# graphic.net
KiCad netlist of a schematic drawn in EAGLE
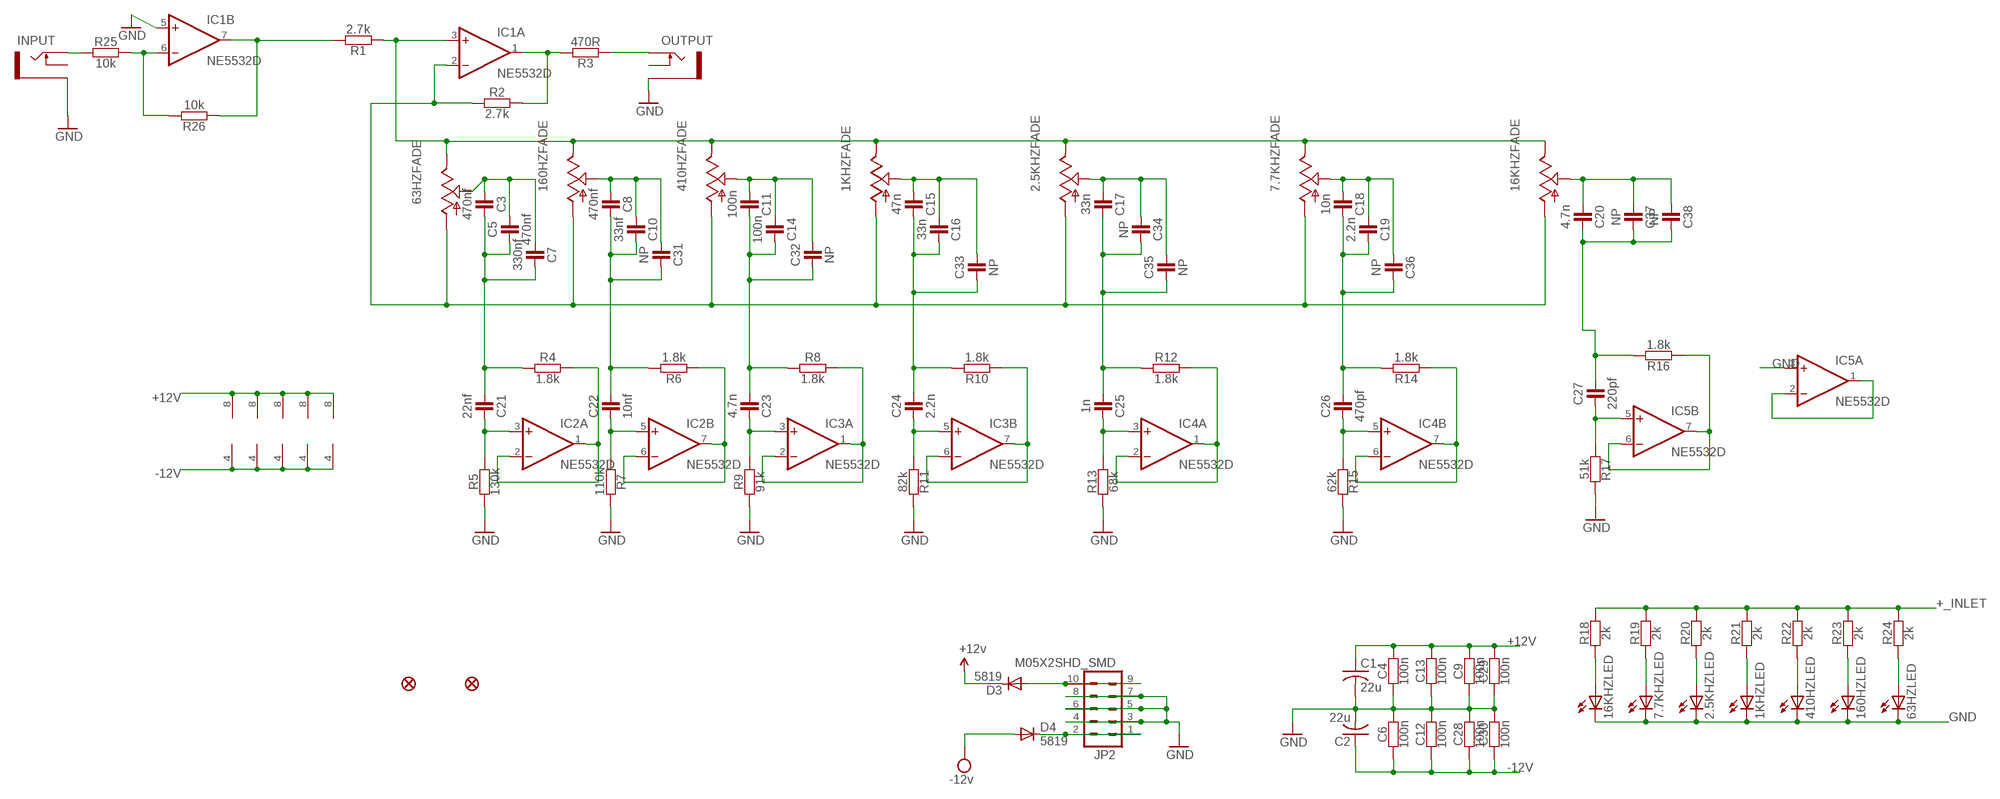
[diagram p0: schematic, sheet 1]

(export (version "E")
  (design (tool "Eeschema 10.0.6"))
  (components
    (comp (ref "1KHZ")
      (value "ALPHA_20MM_ILLUM_FADER")
      (footprint "eagle-import:ALPHA_ILL_FADER_20MM_REV2")
      (libsource (lib "eagle-import") (part "ALPHA_20MM_ILLUM_FADER"))
    )
    (comp (ref "2.5KHZ")
      (value "ALPHA_20MM_ILLUM_FADER")
      (footprint "eagle-import:ALPHA_ILL_FADER_20MM_REV2")
      (libsource (lib "eagle-import") (part "ALPHA_20MM_ILLUM_FADER"))
    )
    (comp (ref "7.7KHZ")
      (value "ALPHA_20MM_ILLUM_FADER")
      (footprint "eagle-import:ALPHA_ILL_FADER_20MM_REV2")
      (libsource (lib "eagle-import") (part "ALPHA_20MM_ILLUM_FADER"))
    )
    (comp (ref "16KHZ")
      (value "ALPHA_20MM_ILLUM_FADER")
      (footprint "eagle-import:ALPHA_ILL_FADER_20MM_REV2")
      (libsource (lib "eagle-import") (part "ALPHA_20MM_ILLUM_FADER"))
    )
    (comp (ref "63HZ")
      (value "ALPHA_20MM_ILLUM_FADER")
      (footprint "eagle-import:ALPHA_ILL_FADER_20MM_REV2")
      (libsource (lib "eagle-import") (part "ALPHA_20MM_ILLUM_FADER"))
    )
    (comp (ref "160HZ")
      (value "ALPHA_20MM_ILLUM_FADER")
      (footprint "eagle-import:ALPHA_ILL_FADER_20MM_REV2")
      (libsource (lib "eagle-import") (part "ALPHA_20MM_ILLUM_FADER"))
    )
    (comp (ref "410HZ")
      (value "ALPHA_20MM_ILLUM_FADER")
      (footprint "eagle-import:ALPHA_ILL_FADER_20MM_REV2")
      (libsource (lib "eagle-import") (part "ALPHA_20MM_ILLUM_FADER"))
    )
    (comp (ref "C1")
      (value "22u")
      (footprint "eagle-import:C1206")
      (libsource (lib "eagle-import") (part "C-USC1206"))
    )
    (comp (ref "C2")
      (value "22u")
      (footprint "eagle-import:C1206")
      (libsource (lib "eagle-import") (part "C-USC1206"))
    )
    (comp (ref "C3")
      (value "470nf")
      (footprint "eagle-import:C0805")
      (libsource (lib "eagle-import") (part "CAPACITOR-0805"))
    )
    (comp (ref "C4")
      (value "100n")
      (footprint "eagle-import:C0805")
      (libsource (lib "eagle-import") (part "RESISTOR-0805"))
    )
    (comp (ref "C5")
      (value "470nf")
      (footprint "eagle-import:C0805")
      (libsource (lib "eagle-import") (part "CAPACITOR-0805"))
    )
    (comp (ref "C6")
      (value "100n")
      (footprint "eagle-import:C0805")
      (libsource (lib "eagle-import") (part "RESISTOR-0805"))
    )
    (comp (ref "C7")
      (value "330nf")
      (footprint "eagle-import:C0805")
      (libsource (lib "eagle-import") (part "CAPACITOR-0805"))
    )
    (comp (ref "C8")
      (value "470nf")
      (footprint "eagle-import:C0805")
      (libsource (lib "eagle-import") (part "CAPACITOR-0805"))
    )
    (comp (ref "C9")
      (value "100n")
      (footprint "eagle-import:C0805")
      (libsource (lib "eagle-import") (part "RESISTOR-0805"))
    )
    (comp (ref "C10")
      (value "33nf")
      (footprint "eagle-import:C0805")
      (libsource (lib "eagle-import") (part "CAPACITOR-0805"))
    )
    (comp (ref "C11")
      (value "100n")
      (footprint "eagle-import:C0805")
      (libsource (lib "eagle-import") (part "CAPACITOR-0805"))
    )
    (comp (ref "C12")
      (value "100n")
      (footprint "eagle-import:C0805")
      (libsource (lib "eagle-import") (part "RESISTOR-0805"))
    )
    (comp (ref "C13")
      (value "100n")
      (footprint "eagle-import:C0805")
      (libsource (lib "eagle-import") (part "RESISTOR-0805"))
    )
    (comp (ref "C14")
      (value "100n")
      (footprint "eagle-import:C0805")
      (libsource (lib "eagle-import") (part "CAPACITOR-0805"))
    )
    (comp (ref "C15")
      (value "47n")
      (footprint "eagle-import:C0805")
      (libsource (lib "eagle-import") (part "CAPACITOR-0805"))
    )
    (comp (ref "C16")
      (value "33n")
      (footprint "eagle-import:C0805")
      (libsource (lib "eagle-import") (part "CAPACITOR-0805"))
    )
    (comp (ref "C17")
      (value "33n")
      (footprint "eagle-import:C0805")
      (libsource (lib "eagle-import") (part "CAPACITOR-0805"))
    )
    (comp (ref "C18")
      (value "10n")
      (footprint "eagle-import:C0805")
      (libsource (lib "eagle-import") (part "CAPACITOR-0805"))
    )
    (comp (ref "C19")
      (value "2.2n")
      (footprint "eagle-import:C0805")
      (libsource (lib "eagle-import") (part "CAPACITOR-0805"))
    )
    (comp (ref "C20")
      (value "4.7n")
      (footprint "eagle-import:C0805")
      (libsource (lib "eagle-import") (part "CAPACITOR-0805"))
    )
    (comp (ref "C21")
      (value "22nf")
      (footprint "eagle-import:C0805")
      (libsource (lib "eagle-import") (part "CAPACITOR-0805"))
    )
    (comp (ref "C22")
      (value "10nf")
      (footprint "eagle-import:C0805")
      (libsource (lib "eagle-import") (part "CAPACITOR-0805"))
    )
    (comp (ref "C23")
      (value "4.7n")
      (footprint "eagle-import:C0805")
      (libsource (lib "eagle-import") (part "CAPACITOR-0805"))
    )
    (comp (ref "C24")
      (value "2.2n")
      (footprint "eagle-import:C0805")
      (libsource (lib "eagle-import") (part "CAPACITOR-0805"))
    )
    (comp (ref "C25")
      (value "1n")
      (footprint "eagle-import:C0805")
      (libsource (lib "eagle-import") (part "CAPACITOR-0805"))
    )
    (comp (ref "C26")
      (value "470pf")
      (footprint "eagle-import:C0805")
      (libsource (lib "eagle-import") (part "CAPACITOR-0805"))
    )
    (comp (ref "C27")
      (value "220pf")
      (footprint "eagle-import:C0805")
      (libsource (lib "eagle-import") (part "CAPACITOR-0805"))
    )
    (comp (ref "C28")
      (value "100n")
      (footprint "eagle-import:C0805")
      (libsource (lib "eagle-import") (part "RESISTOR-0805"))
    )
    (comp (ref "C29")
      (value "100n")
      (footprint "eagle-import:C0805")
      (libsource (lib "eagle-import") (part "RESISTOR-0805"))
    )
    (comp (ref "C30")
      (value "100n")
      (footprint "eagle-import:C0805")
      (libsource (lib "eagle-import") (part "RESISTOR-0805"))
    )
    (comp (ref "C31")
      (value "NP")
      (footprint "eagle-import:C0805")
      (libsource (lib "eagle-import") (part "CAPACITOR-0805"))
    )
    (comp (ref "C32")
      (value "NP")
      (footprint "eagle-import:C0805")
      (libsource (lib "eagle-import") (part "CAPACITOR-0805"))
    )
    (comp (ref "C33")
      (value "NP")
      (footprint "eagle-import:C0805")
      (libsource (lib "eagle-import") (part "CAPACITOR-0805"))
    )
    (comp (ref "C34")
      (value "NP")
      (footprint "eagle-import:C0805")
      (libsource (lib "eagle-import") (part "CAPACITOR-0805"))
    )
    (comp (ref "C35")
      (value "NP")
      (footprint "eagle-import:C0805")
      (libsource (lib "eagle-import") (part "CAPACITOR-0805"))
    )
    (comp (ref "C36")
      (value "NP")
      (footprint "eagle-import:C0805")
      (libsource (lib "eagle-import") (part "CAPACITOR-0805"))
    )
    (comp (ref "C37")
      (value "NP")
      (footprint "eagle-import:C0805")
      (libsource (lib "eagle-import") (part "CAPACITOR-0805"))
    )
    (comp (ref "C38")
      (value "NP")
      (footprint "eagle-import:C0805")
      (libsource (lib "eagle-import") (part "CAPACITOR-0805"))
    )
    (comp (ref "D3")
      (value "5819")
      (footprint "eagle-import:SOD123")
      (libsource (lib "eagle-import") (part "DIODE-SOD123"))
    )
    (comp (ref "D4")
      (value "5819")
      (footprint "eagle-import:SOD123")
      (libsource (lib "eagle-import") (part "DIODE-SOD123"))
    )
    (comp (ref "FID1")
      (value "FIDUCIAL1.5X3")
      (footprint "eagle-import:FIDUCIAL-1.5X3")
      (libsource (lib "eagle-import") (part "FIDUCIAL1.5X3"))
    )
    (comp (ref "FID2")
      (value "FIDUCIAL1.5X3")
      (footprint "eagle-import:FIDUCIAL-1.5X3")
      (libsource (lib "eagle-import") (part "FIDUCIAL1.5X3"))
    )
    (comp (ref "IC1")
      (value "NE5532D")
      (footprint "eagle-import:SO08")
      (libsource (lib "eagle-import") (part "NE5532D"))
    )
    (comp (ref "IC2")
      (value "NE5532D")
      (footprint "eagle-import:SO08")
      (libsource (lib "eagle-import") (part "NE5532D"))
    )
    (comp (ref "IC3")
      (value "NE5532D")
      (footprint "eagle-import:SO08")
      (libsource (lib "eagle-import") (part "NE5532D"))
    )
    (comp (ref "IC4")
      (value "NE5532D")
      (footprint "eagle-import:SO08")
      (libsource (lib "eagle-import") (part "NE5532D"))
    )
    (comp (ref "IC5")
      (value "NE5532D")
      (footprint "eagle-import:SO08")
      (libsource (lib "eagle-import") (part "NE5532D"))
    )
    (comp (ref "INPUT")
      (value "THONKICONNNEW")
      (footprint "eagle-import:WQP-PJ301M-12_JACK")
      (libsource (lib "eagle-import") (part "THONKICONNNEW"))
    )
    (comp (ref "JP2")
      (value "M05X2SHD_SMD")
      (footprint "eagle-import:2X5-SHROUDED_SMD")
      (libsource (lib "eagle-import") (part "M05X2SHD_SMD"))
    )
    (comp (ref "OUTPUT")
      (value "THONKICONNNEW")
      (footprint "eagle-import:WQP-PJ301M-12_JACK")
      (libsource (lib "eagle-import") (part "THONKICONNNEW"))
    )
    (comp (ref "R1")
      (value "2.7k")
      (footprint "eagle-import:C0805")
      (libsource (lib "eagle-import") (part "RESISTOR-0805"))
    )
    (comp (ref "R2")
      (value "2.7k")
      (footprint "eagle-import:C0805")
      (libsource (lib "eagle-import") (part "RESISTOR-0805"))
    )
    (comp (ref "R3")
      (value "470R")
      (footprint "eagle-import:C0805")
      (libsource (lib "eagle-import") (part "RESISTOR-0805"))
    )
    (comp (ref "R4")
      (value "1.8k")
      (footprint "eagle-import:C0805")
      (libsource (lib "eagle-import") (part "RESISTOR-0805"))
    )
    (comp (ref "R5")
      (value "130k")
      (footprint "eagle-import:C0805")
      (libsource (lib "eagle-import") (part "RESISTOR-0805"))
    )
    (comp (ref "R6")
      (value "1.8k")
      (footprint "eagle-import:C0805")
      (libsource (lib "eagle-import") (part "RESISTOR-0805"))
    )
    (comp (ref "R7")
      (value "110k")
      (footprint "eagle-import:C0805")
      (libsource (lib "eagle-import") (part "RESISTOR-0805"))
    )
    (comp (ref "R8")
      (value "1.8k")
      (footprint "eagle-import:C0805")
      (libsource (lib "eagle-import") (part "RESISTOR-0805"))
    )
    (comp (ref "R9")
      (value "91k")
      (footprint "eagle-import:C0805")
      (libsource (lib "eagle-import") (part "RESISTOR-0805"))
    )
    (comp (ref "R10")
      (value "1.8k")
      (footprint "eagle-import:C0805")
      (libsource (lib "eagle-import") (part "RESISTOR-0805"))
    )
    (comp (ref "R11")
      (value "82k")
      (footprint "eagle-import:C0805")
      (libsource (lib "eagle-import") (part "RESISTOR-0805"))
    )
    (comp (ref "R12")
      (value "1.8k")
      (footprint "eagle-import:C0805")
      (libsource (lib "eagle-import") (part "RESISTOR-0805"))
    )
    (comp (ref "R13")
      (value "68k")
      (footprint "eagle-import:C0805")
      (libsource (lib "eagle-import") (part "RESISTOR-0805"))
    )
    (comp (ref "R14")
      (value "1.8k")
      (footprint "eagle-import:C0805")
      (libsource (lib "eagle-import") (part "RESISTOR-0805"))
    )
    (comp (ref "R15")
      (value "62k")
      (footprint "eagle-import:C0805")
      (libsource (lib "eagle-import") (part "RESISTOR-0805"))
    )
    (comp (ref "R16")
      (value "1.8k")
      (footprint "eagle-import:C0805")
      (libsource (lib "eagle-import") (part "RESISTOR-0805"))
    )
    (comp (ref "R17")
      (value "51k")
      (footprint "eagle-import:C0805")
      (libsource (lib "eagle-import") (part "RESISTOR-0805"))
    )
    (comp (ref "R18")
      (value "2k")
      (footprint "eagle-import:C0805")
      (libsource (lib "eagle-import") (part "RESISTOR-0805"))
    )
    (comp (ref "R19")
      (value "2k")
      (footprint "eagle-import:C0805")
      (libsource (lib "eagle-import") (part "RESISTOR-0805"))
    )
    (comp (ref "R20")
      (value "2k")
      (footprint "eagle-import:C0805")
      (libsource (lib "eagle-import") (part "RESISTOR-0805"))
    )
    (comp (ref "R21")
      (value "2k")
      (footprint "eagle-import:C0805")
      (libsource (lib "eagle-import") (part "RESISTOR-0805"))
    )
    (comp (ref "R22")
      (value "2k")
      (footprint "eagle-import:C0805")
      (libsource (lib "eagle-import") (part "RESISTOR-0805"))
    )
    (comp (ref "R23")
      (value "2k")
      (footprint "eagle-import:C0805")
      (libsource (lib "eagle-import") (part "RESISTOR-0805"))
    )
    (comp (ref "R24")
      (value "2k")
      (footprint "eagle-import:C0805")
      (libsource (lib "eagle-import") (part "RESISTOR-0805"))
    )
    (comp (ref "R25")
      (value "10k")
      (footprint "eagle-import:C0805")
      (libsource (lib "eagle-import") (part "RESISTOR-0805"))
    )
    (comp (ref "R26")
      (value "10k")
      (footprint "eagle-import:C0805")
      (libsource (lib "eagle-import") (part "RESISTOR-0805"))
    )
  )
  (nets
    (net (code "1") (name "+12v") (class "Default")
      (node (ref "C1") (pin "1") (pinfunction "1_1") (pintype "passive"))
      (node (ref "C13") (pin "2") (pinfunction "2_2") (pintype "passive"))
      (node (ref "C29") (pin "2") (pinfunction "2_2") (pintype "passive"))
      (node (ref "C4") (pin "2") (pinfunction "2_2") (pintype "passive"))
      (node (ref "C9") (pin "2") (pinfunction "2_2") (pintype "passive"))
      (node (ref "D3") (pin "C") (pinfunction "C_C") (pintype "passive"))
      (node (ref "IC1") (pin "8") (pinfunction "V+_8") (pintype "power_in"))
      (node (ref "IC2") (pin "8") (pinfunction "V+_8") (pintype "power_in"))
      (node (ref "IC3") (pin "8") (pinfunction "V+_8") (pintype "power_in"))
      (node (ref "IC4") (pin "8") (pinfunction "V+_8") (pintype "power_in"))
      (node (ref "IC5") (pin "8") (pinfunction "V+_8") (pintype "power_in"))
    )
    (net (code "2") (name "-12v") (class "Default")
      (node (ref "C12") (pin "1") (pinfunction "1_1") (pintype "passive"))
      (node (ref "C2") (pin "1") (pinfunction "1_1") (pintype "passive"))
      (node (ref "C28") (pin "1") (pinfunction "1_1") (pintype "passive"))
      (node (ref "C30") (pin "1") (pinfunction "1_1") (pintype "passive"))
      (node (ref "C6") (pin "1") (pinfunction "1_1") (pintype "passive"))
      (node (ref "D4") (pin "A") (pinfunction "A_A") (pintype "passive"))
      (node (ref "IC1") (pin "4") (pinfunction "V-_4") (pintype "power_in"))
      (node (ref "IC2") (pin "4") (pinfunction "V-_4") (pintype "power_in"))
      (node (ref "IC3") (pin "4") (pinfunction "V-_4") (pintype "power_in"))
      (node (ref "IC4") (pin "4") (pinfunction "V-_4") (pintype "power_in"))
      (node (ref "IC5") (pin "4") (pinfunction "V-_4") (pintype "power_in"))
    )
    (net (code "3") (name "/+_INLET") (class "Default")
      (node (ref "D3") (pin "A") (pinfunction "A_A") (pintype "passive"))
      (node (ref "JP2") (pin "10") (pinfunction "10_10") (pintype "passive"))
      (node (ref "JP2") (pin "9") (pinfunction "9_9") (pintype "passive"))
      (node (ref "R18") (pin "2") (pinfunction "2_2") (pintype "passive"))
      (node (ref "R19") (pin "2") (pinfunction "2_2") (pintype "passive"))
      (node (ref "R20") (pin "2") (pinfunction "2_2") (pintype "passive"))
      (node (ref "R21") (pin "2") (pinfunction "2_2") (pintype "passive"))
      (node (ref "R22") (pin "2") (pinfunction "2_2") (pintype "passive"))
      (node (ref "R23") (pin "2") (pinfunction "2_2") (pintype "passive"))
      (node (ref "R24") (pin "2") (pinfunction "2_2") (pintype "passive"))
    )
    (net (code "4") (name "GND") (class "Default")
      (node (ref "160HZ") (pin "E") (pinfunction "C_E") (pintype "passive"))
      (node (ref "16KHZ") (pin "E") (pinfunction "C_E") (pintype "passive"))
      (node (ref "1KHZ") (pin "E") (pinfunction "C_E") (pintype "passive"))
      (node (ref "2.5KHZ") (pin "E") (pinfunction "C_E") (pintype "passive"))
      (node (ref "410HZ") (pin "E") (pinfunction "C_E") (pintype "passive"))
      (node (ref "63HZ") (pin "E") (pinfunction "C_E") (pintype "passive"))
      (node (ref "7.7KHZ") (pin "E") (pinfunction "C_E") (pintype "passive"))
      (node (ref "C1") (pin "2") (pinfunction "2_2") (pintype "passive"))
      (node (ref "C12") (pin "2") (pinfunction "2_2") (pintype "passive"))
      (node (ref "C13") (pin "1") (pinfunction "1_1") (pintype "passive"))
      (node (ref "C2") (pin "2") (pinfunction "2_2") (pintype "passive"))
      (node (ref "C28") (pin "2") (pinfunction "2_2") (pintype "passive"))
      (node (ref "C29") (pin "1") (pinfunction "1_1") (pintype "passive"))
      (node (ref "C30") (pin "2") (pinfunction "2_2") (pintype "passive"))
      (node (ref "C4") (pin "1") (pinfunction "1_1") (pintype "passive"))
      (node (ref "C6") (pin "2") (pinfunction "2_2") (pintype "passive"))
      (node (ref "C9") (pin "1") (pinfunction "1_1") (pintype "passive"))
      (node (ref "IC1") (pin "5") (pinfunction "+IN_5") (pintype "input"))
      (node (ref "IC5") (pin "3") (pinfunction "+IN_3") (pintype "input"))
      (node (ref "INPUT") (pin "P$3_SLEEVE") (pinfunction "SLEEVE_P$3_SLEEVE") (pintype "passive"))
      (node (ref "JP2") (pin "3") (pinfunction "3_3") (pintype "passive"))
      (node (ref "JP2") (pin "4") (pinfunction "4_4") (pintype "passive"))
      (node (ref "JP2") (pin "5") (pinfunction "5_5") (pintype "passive"))
      (node (ref "JP2") (pin "6") (pinfunction "6_6") (pintype "passive"))
      (node (ref "JP2") (pin "7") (pinfunction "7_7") (pintype "passive"))
      (node (ref "JP2") (pin "8") (pinfunction "8_8") (pintype "passive"))
      (node (ref "OUTPUT") (pin "P$3_SLEEVE") (pinfunction "SLEEVE_P$3_SLEEVE") (pintype "passive"))
      (node (ref "R11") (pin "2") (pinfunction "2_2") (pintype "passive"))
      (node (ref "R13") (pin "1") (pinfunction "1_1") (pintype "passive"))
      (node (ref "R15") (pin "2") (pinfunction "2_2") (pintype "passive"))
      (node (ref "R17") (pin "2") (pinfunction "2_2") (pintype "passive"))
      (node (ref "R5") (pin "1") (pinfunction "1_1") (pintype "passive"))
      (node (ref "R7") (pin "2") (pinfunction "2_2") (pintype "passive"))
      (node (ref "R9") (pin "1") (pinfunction "1_1") (pintype "passive"))
    )
    (net (code "5") (name "Net-(1KHZA-S)") (class "Default")
      (node (ref "1KHZ") (pin "2") (pinfunction "S_2") (pintype "passive"))
      (node (ref "C15") (pin "1") (pinfunction "1_1") (pintype "passive"))
      (node (ref "C16") (pin "1") (pinfunction "1_1") (pintype "passive"))
      (node (ref "C33") (pin "2") (pinfunction "2_2") (pintype "passive"))
    )
    (net (code "6") (name "Net-(1KHZB-A)") (class "Default")
      (node (ref "1KHZ") (pin "B") (pinfunction "A_B") (pintype "passive"))
      (node (ref "R21") (pin "1") (pinfunction "1_1") (pintype "passive"))
    )
    (net (code "7") (name "Net-(2.5KHZA-S)") (class "Default")
      (node (ref "2.5KHZ") (pin "2") (pinfunction "S_2") (pintype "passive"))
      (node (ref "C17") (pin "1") (pinfunction "1_1") (pintype "passive"))
      (node (ref "C34") (pin "1") (pinfunction "1_1") (pintype "passive"))
      (node (ref "C35") (pin "2") (pinfunction "2_2") (pintype "passive"))
    )
    (net (code "8") (name "Net-(2.5KHZB-A)") (class "Default")
      (node (ref "2.5KHZ") (pin "B") (pinfunction "A_B") (pintype "passive"))
      (node (ref "R20") (pin "1") (pinfunction "1_1") (pintype "passive"))
    )
    (net (code "9") (name "Net-(7.7KHZA-S)") (class "Default")
      (node (ref "7.7KHZ") (pin "2") (pinfunction "S_2") (pintype "passive"))
      (node (ref "C18") (pin "1") (pinfunction "1_1") (pintype "passive"))
      (node (ref "C19") (pin "1") (pinfunction "1_1") (pintype "passive"))
      (node (ref "C36") (pin "1") (pinfunction "1_1") (pintype "passive"))
    )
    (net (code "10") (name "Net-(7.7KHZB-A)") (class "Default")
      (node (ref "7.7KHZ") (pin "B") (pinfunction "A_B") (pintype "passive"))
      (node (ref "R19") (pin "1") (pinfunction "1_1") (pintype "passive"))
    )
    (net (code "11") (name "Net-(16KHZA-S)") (class "Default")
      (node (ref "16KHZ") (pin "2") (pinfunction "S_2") (pintype "passive"))
      (node (ref "C20") (pin "1") (pinfunction "1_1") (pintype "passive"))
      (node (ref "C37") (pin "1") (pinfunction "1_1") (pintype "passive"))
      (node (ref "C38") (pin "1") (pinfunction "1_1") (pintype "passive"))
    )
    (net (code "12") (name "Net-(16KHZB-A)") (class "Default")
      (node (ref "16KHZ") (pin "B") (pinfunction "A_B") (pintype "passive"))
      (node (ref "R18") (pin "1") (pinfunction "1_1") (pintype "passive"))
    )
    (net (code "13") (name "Net-(63HZA-S)") (class "Default")
      (node (ref "63HZ") (pin "2") (pinfunction "S_2") (pintype "passive"))
      (node (ref "C3") (pin "1") (pinfunction "1_1") (pintype "passive"))
      (node (ref "C5") (pin "2") (pinfunction "2_2") (pintype "passive"))
      (node (ref "C7") (pin "1") (pinfunction "1_1") (pintype "passive"))
    )
    (net (code "14") (name "Net-(63HZB-A)") (class "Default")
      (node (ref "63HZ") (pin "B") (pinfunction "A_B") (pintype "passive"))
      (node (ref "R24") (pin "1") (pinfunction "1_1") (pintype "passive"))
    )
    (net (code "15") (name "Net-(160HZA-A)") (class "Default")
      (node (ref "160HZ") (pin "3") (pinfunction "A_3") (pintype "passive"))
      (node (ref "16KHZ") (pin "3") (pinfunction "A_3") (pintype "passive"))
      (node (ref "1KHZ") (pin "3") (pinfunction "A_3") (pintype "passive"))
      (node (ref "2.5KHZ") (pin "3") (pinfunction "A_3") (pintype "passive"))
      (node (ref "410HZ") (pin "3") (pinfunction "A_3") (pintype "passive"))
      (node (ref "63HZ") (pin "3") (pinfunction "A_3") (pintype "passive"))
      (node (ref "7.7KHZ") (pin "3") (pinfunction "A_3") (pintype "passive"))
      (node (ref "IC1") (pin "2") (pinfunction "-IN_2") (pintype "input"))
      (node (ref "R2") (pin "1") (pinfunction "1_1") (pintype "passive"))
    )
    (net (code "16") (name "Net-(160HZA-E)") (class "Default")
      (node (ref "160HZ") (pin "1") (pinfunction "E_1") (pintype "passive"))
      (node (ref "16KHZ") (pin "1") (pinfunction "E_1") (pintype "passive"))
      (node (ref "1KHZ") (pin "1") (pinfunction "E_1") (pintype "passive"))
      (node (ref "2.5KHZ") (pin "1") (pinfunction "E_1") (pintype "passive"))
      (node (ref "410HZ") (pin "1") (pinfunction "E_1") (pintype "passive"))
      (node (ref "63HZ") (pin "1") (pinfunction "E_1") (pintype "passive"))
      (node (ref "7.7KHZ") (pin "1") (pinfunction "E_1") (pintype "passive"))
      (node (ref "IC1") (pin "3") (pinfunction "+IN_3") (pintype "input"))
      (node (ref "R1") (pin "1") (pinfunction "1_1") (pintype "passive"))
    )
    (net (code "17") (name "Net-(160HZA-S)") (class "Default")
      (node (ref "160HZ") (pin "2") (pinfunction "S_2") (pintype "passive"))
      (node (ref "C10") (pin "1") (pinfunction "1_1") (pintype "passive"))
      (node (ref "C31") (pin "1") (pinfunction "1_1") (pintype "passive"))
      (node (ref "C8") (pin "1") (pinfunction "1_1") (pintype "passive"))
    )
    (net (code "18") (name "Net-(160HZB-A)") (class "Default")
      (node (ref "160HZ") (pin "B") (pinfunction "A_B") (pintype "passive"))
      (node (ref "R23") (pin "1") (pinfunction "1_1") (pintype "passive"))
    )
    (net (code "19") (name "Net-(410HZA-S)") (class "Default")
      (node (ref "410HZ") (pin "2") (pinfunction "S_2") (pintype "passive"))
      (node (ref "C11") (pin "1") (pinfunction "1_1") (pintype "passive"))
      (node (ref "C14") (pin "1") (pinfunction "1_1") (pintype "passive"))
      (node (ref "C32") (pin "2") (pinfunction "2_2") (pintype "passive"))
    )
    (net (code "20") (name "Net-(410HZB-A)") (class "Default")
      (node (ref "410HZ") (pin "B") (pinfunction "A_B") (pintype "passive"))
      (node (ref "R22") (pin "1") (pinfunction "1_1") (pintype "passive"))
    )
    (net (code "21") (name "Net-(C10-Pad2)") (class "Default")
      (node (ref "C10") (pin "2") (pinfunction "2_2") (pintype "passive"))
      (node (ref "C22") (pin "2") (pinfunction "2_2") (pintype "passive"))
      (node (ref "C31") (pin "2") (pinfunction "2_2") (pintype "passive"))
      (node (ref "C8") (pin "2") (pinfunction "2_2") (pintype "passive"))
      (node (ref "R6") (pin "2") (pinfunction "2_2") (pintype "passive"))
    )
    (net (code "22") (name "Net-(C11-Pad2)") (class "Default")
      (node (ref "C11") (pin "2") (pinfunction "2_2") (pintype "passive"))
      (node (ref "C14") (pin "2") (pinfunction "2_2") (pintype "passive"))
      (node (ref "C23") (pin "1") (pinfunction "1_1") (pintype "passive"))
      (node (ref "C32") (pin "1") (pinfunction "1_1") (pintype "passive"))
      (node (ref "R8") (pin "1") (pinfunction "1_1") (pintype "passive"))
    )
    (net (code "23") (name "Net-(C15-Pad2)") (class "Default")
      (node (ref "C15") (pin "2") (pinfunction "2_2") (pintype "passive"))
      (node (ref "C16") (pin "2") (pinfunction "2_2") (pintype "passive"))
      (node (ref "C24") (pin "2") (pinfunction "2_2") (pintype "passive"))
      (node (ref "C33") (pin "1") (pinfunction "1_1") (pintype "passive"))
      (node (ref "R10") (pin "2") (pinfunction "2_2") (pintype "passive"))
    )
    (net (code "24") (name "Net-(C17-Pad2)") (class "Default")
      (node (ref "C17") (pin "2") (pinfunction "2_2") (pintype "passive"))
      (node (ref "C25") (pin "1") (pinfunction "1_1") (pintype "passive"))
      (node (ref "C34") (pin "2") (pinfunction "2_2") (pintype "passive"))
      (node (ref "C35") (pin "1") (pinfunction "1_1") (pintype "passive"))
      (node (ref "R12") (pin "1") (pinfunction "1_1") (pintype "passive"))
    )
    (net (code "25") (name "Net-(C18-Pad2)") (class "Default")
      (node (ref "C18") (pin "2") (pinfunction "2_2") (pintype "passive"))
      (node (ref "C19") (pin "2") (pinfunction "2_2") (pintype "passive"))
      (node (ref "C26") (pin "2") (pinfunction "2_2") (pintype "passive"))
      (node (ref "C36") (pin "2") (pinfunction "2_2") (pintype "passive"))
      (node (ref "R14") (pin "2") (pinfunction "2_2") (pintype "passive"))
    )
    (net (code "26") (name "Net-(C20-Pad2)") (class "Default")
      (node (ref "C20") (pin "2") (pinfunction "2_2") (pintype "passive"))
      (node (ref "C27") (pin "2") (pinfunction "2_2") (pintype "passive"))
      (node (ref "C37") (pin "2") (pinfunction "2_2") (pintype "passive"))
      (node (ref "C38") (pin "2") (pinfunction "2_2") (pintype "passive"))
      (node (ref "R16") (pin "2") (pinfunction "2_2") (pintype "passive"))
    )
    (net (code "27") (name "Net-(C21-Pad1)") (class "Default")
      (node (ref "C21") (pin "1") (pinfunction "1_1") (pintype "passive"))
      (node (ref "C3") (pin "2") (pinfunction "2_2") (pintype "passive"))
      (node (ref "C5") (pin "1") (pinfunction "1_1") (pintype "passive"))
      (node (ref "C7") (pin "2") (pinfunction "2_2") (pintype "passive"))
      (node (ref "R4") (pin "1") (pinfunction "1_1") (pintype "passive"))
    )
    (net (code "28") (name "Net-(D4-PadC)") (class "Default")
      (node (ref "D4") (pin "C") (pinfunction "C_C") (pintype "passive"))
      (node (ref "JP2") (pin "1") (pinfunction "1_1") (pintype "passive"))
      (node (ref "JP2") (pin "2") (pinfunction "2_2") (pintype "passive"))
    )
    (net (code "29") (name "Net-(IC1A-OUT)") (class "Default")
      (node (ref "IC1") (pin "1") (pinfunction "OUT_1") (pintype "output"))
      (node (ref "R2") (pin "2") (pinfunction "2_2") (pintype "passive"))
      (node (ref "R3") (pin "2") (pinfunction "2_2") (pintype "passive"))
    )
    (net (code "30") (name "Net-(IC1B--IN)") (class "Default")
      (node (ref "IC1") (pin "6") (pinfunction "-IN_6") (pintype "input"))
      (node (ref "R25") (pin "2") (pinfunction "2_2") (pintype "passive"))
      (node (ref "R26") (pin "2") (pinfunction "2_2") (pintype "passive"))
    )
    (net (code "31") (name "Net-(IC1B-OUT)") (class "Default")
      (node (ref "IC1") (pin "7") (pinfunction "OUT_7") (pintype "output"))
      (node (ref "R1") (pin "2") (pinfunction "2_2") (pintype "passive"))
      (node (ref "R26") (pin "1") (pinfunction "1_1") (pintype "passive"))
    )
    (net (code "32") (name "Net-(IC2A-+IN)") (class "Default")
      (node (ref "C21") (pin "2") (pinfunction "2_2") (pintype "passive"))
      (node (ref "IC2") (pin "3") (pinfunction "+IN_3") (pintype "input"))
      (node (ref "R5") (pin "2") (pinfunction "2_2") (pintype "passive"))
    )
    (net (code "33") (name "Net-(IC2A--IN)") (class "Default")
      (node (ref "IC2") (pin "1") (pinfunction "OUT_1") (pintype "output"))
      (node (ref "IC2") (pin "2") (pinfunction "-IN_2") (pintype "input"))
      (node (ref "R4") (pin "2") (pinfunction "2_2") (pintype "passive"))
    )
    (net (code "34") (name "Net-(IC2B-+IN)") (class "Default")
      (node (ref "C22") (pin "1") (pinfunction "1_1") (pintype "passive"))
      (node (ref "IC2") (pin "5") (pinfunction "+IN_5") (pintype "input"))
      (node (ref "R7") (pin "1") (pinfunction "1_1") (pintype "passive"))
    )
    (net (code "35") (name "Net-(IC2B--IN)") (class "Default")
      (node (ref "IC2") (pin "6") (pinfunction "-IN_6") (pintype "input"))
      (node (ref "IC2") (pin "7") (pinfunction "OUT_7") (pintype "output"))
      (node (ref "R6") (pin "1") (pinfunction "1_1") (pintype "passive"))
    )
    (net (code "36") (name "Net-(IC3A-+IN)") (class "Default")
      (node (ref "C23") (pin "2") (pinfunction "2_2") (pintype "passive"))
      (node (ref "IC3") (pin "3") (pinfunction "+IN_3") (pintype "input"))
      (node (ref "R9") (pin "2") (pinfunction "2_2") (pintype "passive"))
    )
    (net (code "37") (name "Net-(IC3A--IN)") (class "Default")
      (node (ref "IC3") (pin "1") (pinfunction "OUT_1") (pintype "output"))
      (node (ref "IC3") (pin "2") (pinfunction "-IN_2") (pintype "input"))
      (node (ref "R8") (pin "2") (pinfunction "2_2") (pintype "passive"))
    )
    (net (code "38") (name "Net-(IC3B-+IN)") (class "Default")
      (node (ref "C24") (pin "1") (pinfunction "1_1") (pintype "passive"))
      (node (ref "IC3") (pin "5") (pinfunction "+IN_5") (pintype "input"))
      (node (ref "R11") (pin "1") (pinfunction "1_1") (pintype "passive"))
    )
    (net (code "39") (name "Net-(IC3B--IN)") (class "Default")
      (node (ref "IC3") (pin "6") (pinfunction "-IN_6") (pintype "input"))
      (node (ref "IC3") (pin "7") (pinfunction "OUT_7") (pintype "output"))
      (node (ref "R10") (pin "1") (pinfunction "1_1") (pintype "passive"))
    )
    (net (code "40") (name "Net-(IC4A-+IN)") (class "Default")
      (node (ref "C25") (pin "2") (pinfunction "2_2") (pintype "passive"))
      (node (ref "IC4") (pin "3") (pinfunction "+IN_3") (pintype "input"))
      (node (ref "R13") (pin "2") (pinfunction "2_2") (pintype "passive"))
    )
    (net (code "41") (name "Net-(IC4A--IN)") (class "Default")
      (node (ref "IC4") (pin "1") (pinfunction "OUT_1") (pintype "output"))
      (node (ref "IC4") (pin "2") (pinfunction "-IN_2") (pintype "input"))
      (node (ref "R12") (pin "2") (pinfunction "2_2") (pintype "passive"))
    )
    (net (code "42") (name "Net-(IC4B-+IN)") (class "Default")
      (node (ref "C26") (pin "1") (pinfunction "1_1") (pintype "passive"))
      (node (ref "IC4") (pin "5") (pinfunction "+IN_5") (pintype "input"))
      (node (ref "R15") (pin "1") (pinfunction "1_1") (pintype "passive"))
    )
    (net (code "43") (name "Net-(IC4B--IN)") (class "Default")
      (node (ref "IC4") (pin "6") (pinfunction "-IN_6") (pintype "input"))
      (node (ref "IC4") (pin "7") (pinfunction "OUT_7") (pintype "output"))
      (node (ref "R14") (pin "1") (pinfunction "1_1") (pintype "passive"))
    )
    (net (code "44") (name "Net-(IC5A--IN)") (class "Default")
      (node (ref "IC5") (pin "1") (pinfunction "OUT_1") (pintype "output"))
      (node (ref "IC5") (pin "2") (pinfunction "-IN_2") (pintype "input"))
    )
    (net (code "45") (name "Net-(IC5B-+IN)") (class "Default")
      (node (ref "C27") (pin "1") (pinfunction "1_1") (pintype "passive"))
      (node (ref "IC5") (pin "5") (pinfunction "+IN_5") (pintype "input"))
      (node (ref "R17") (pin "1") (pinfunction "1_1") (pintype "passive"))
    )
    (net (code "46") (name "Net-(IC5B--IN)") (class "Default")
      (node (ref "IC5") (pin "6") (pinfunction "-IN_6") (pintype "input"))
      (node (ref "IC5") (pin "7") (pinfunction "OUT_7") (pintype "output"))
      (node (ref "R16") (pin "1") (pinfunction "1_1") (pintype "passive"))
    )
    (net (code "47") (name "Net-(INPUT-TIP)") (class "Default")
      (node (ref "INPUT") (pin "P$1_TIP") (pinfunction "TIP_P$1_TIP") (pintype "passive"))
      (node (ref "R25") (pin "1") (pinfunction "1_1") (pintype "passive"))
    )
    (net (code "48") (name "Net-(OUTPUT-TIP)") (class "Default")
      (node (ref "OUTPUT") (pin "P$1_TIP") (pinfunction "TIP_P$1_TIP") (pintype "passive"))
      (node (ref "R3") (pin "1") (pinfunction "1_1") (pintype "passive"))
    )
    (net (code "49") (name "unconnected-(INPUT-SWITCH-PadP$2_SWITCH)") (class "Default")
      (node (ref "INPUT") (pin "P$2_SWITCH") (pinfunction "SWITCH_P$2_SWITCH") (pintype "passive"))
    )
    (net (code "50") (name "unconnected-(OUTPUT-SWITCH-PadP$2_SWITCH)") (class "Default")
      (node (ref "OUTPUT") (pin "P$2_SWITCH") (pinfunction "SWITCH_P$2_SWITCH") (pintype "passive"))
    )
  )
)
